# Power_Board.net
KiCad netlist of a schematic drawn in EAGLE
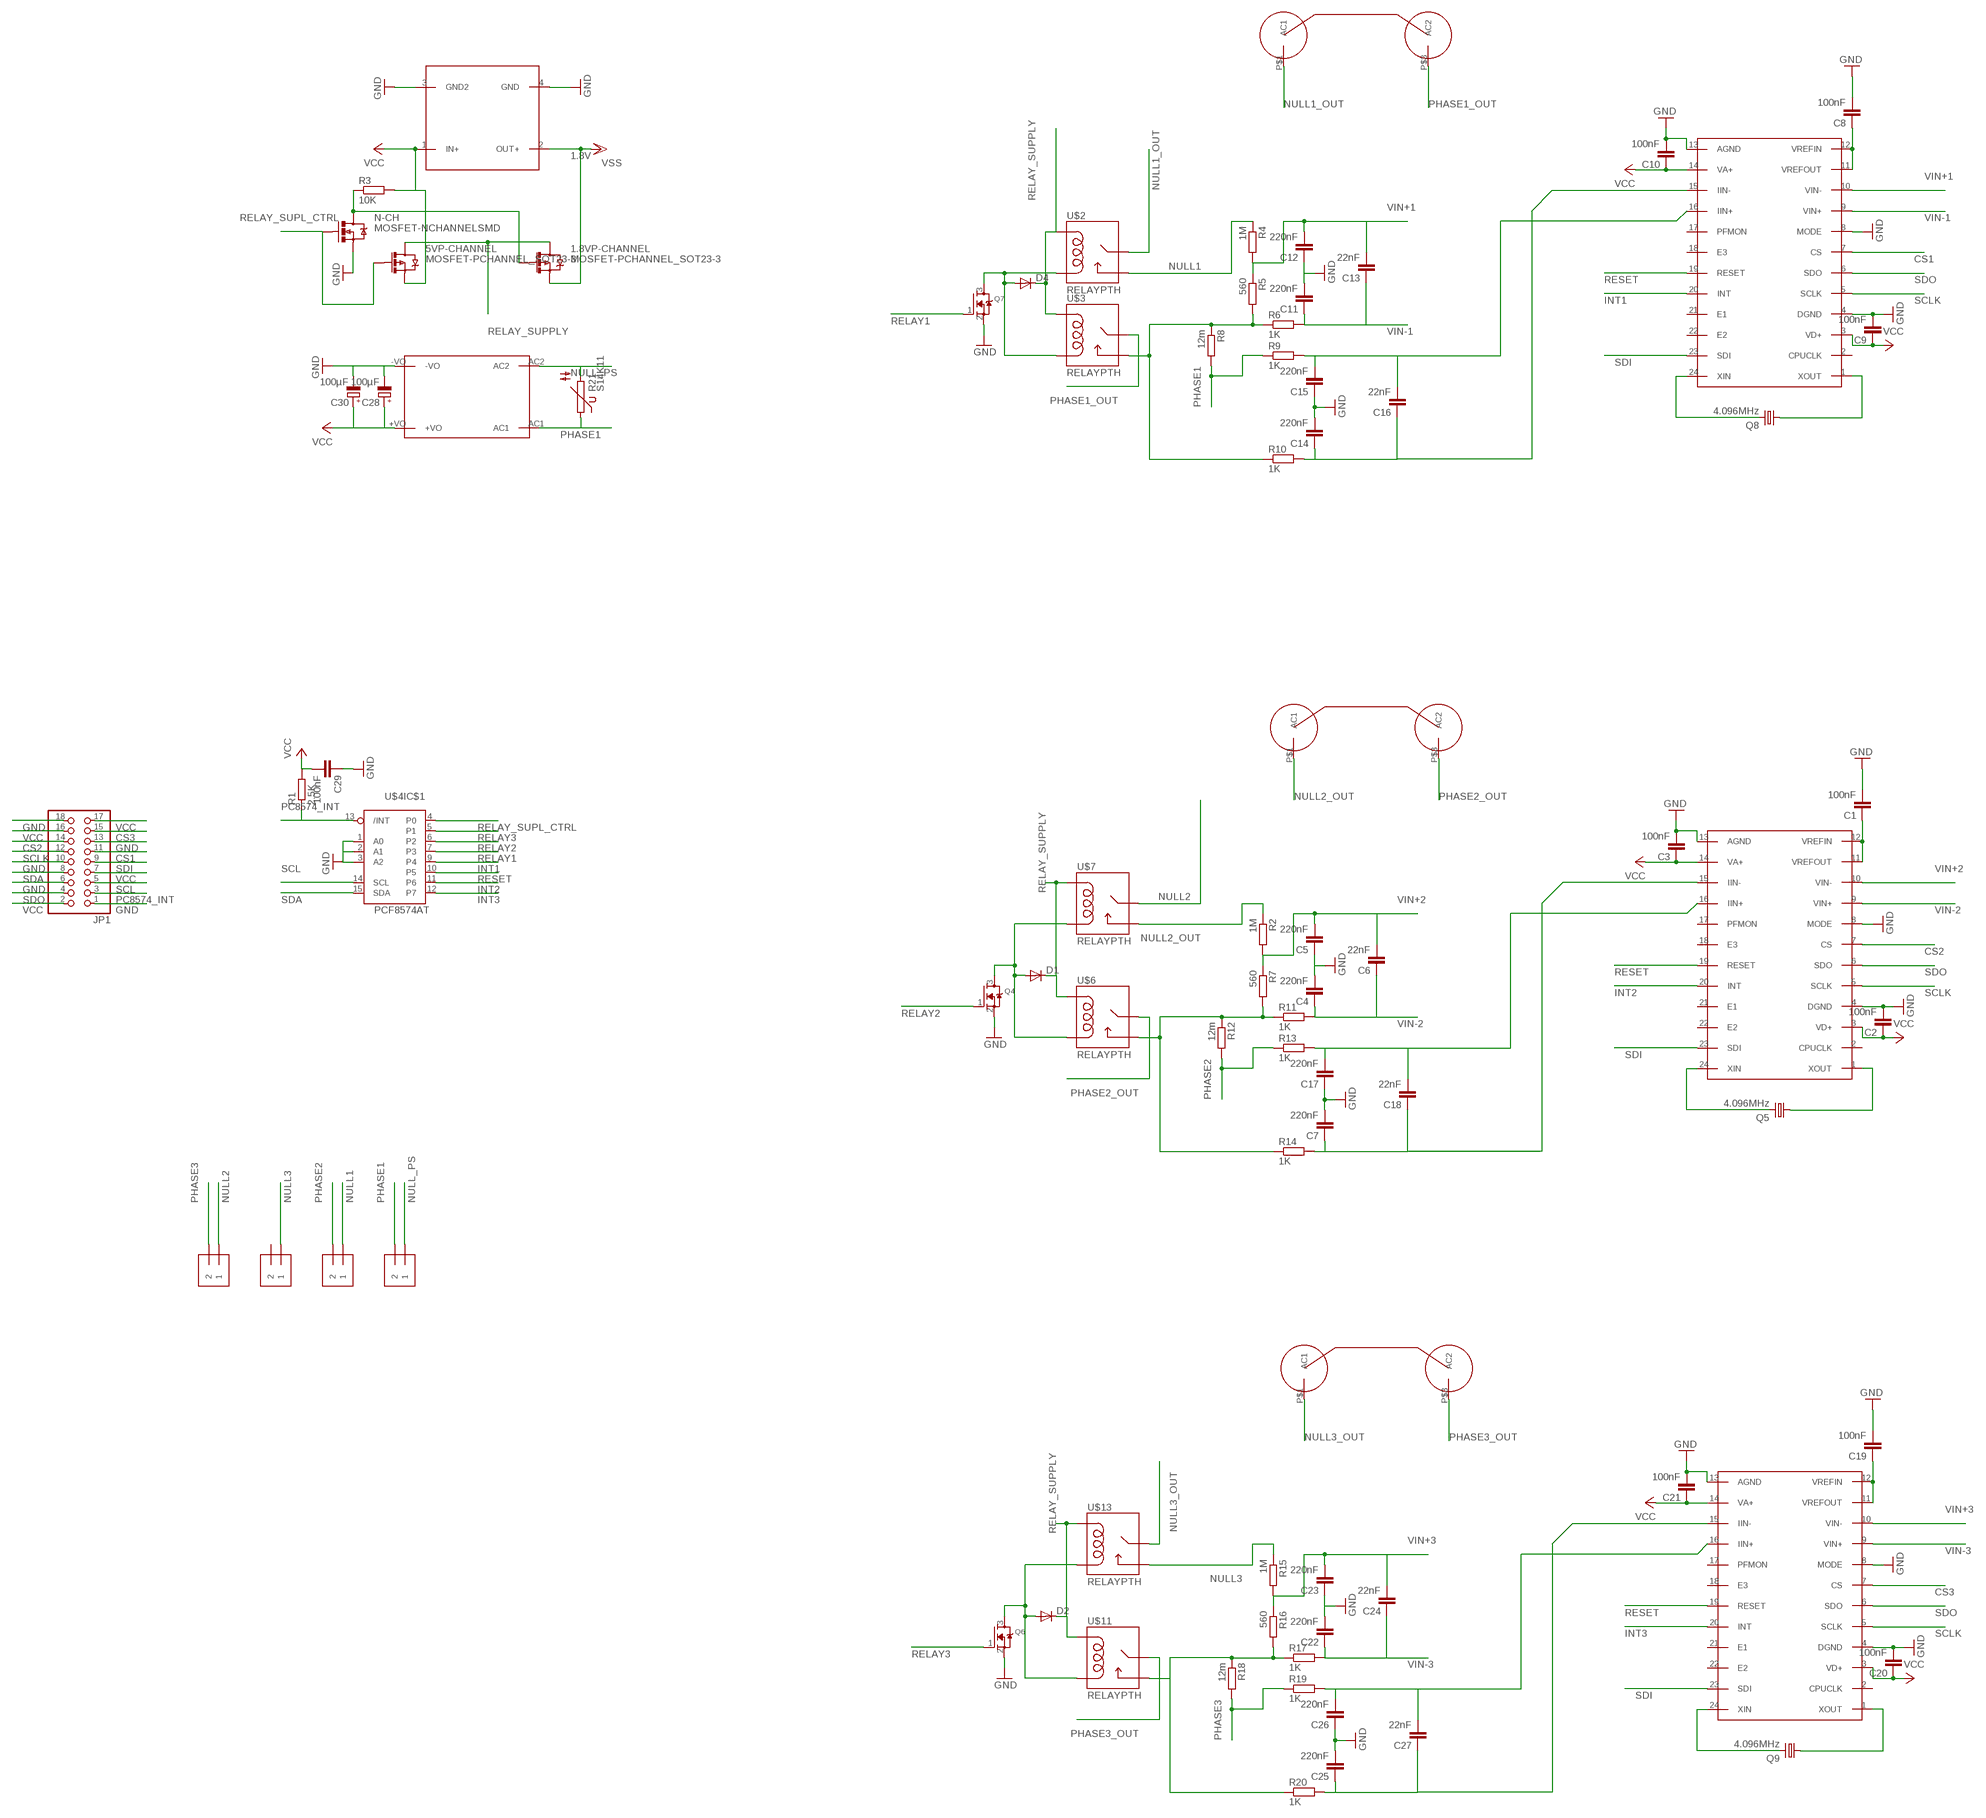
[diagram p0: schematic, sheet 1]

(export (version "E")
  (design (tool "Eeschema 10.0.6"))
  (components
    (comp (ref "1.8VP-CHANNEL")
      (value "MOSFET-PCHANNEL_SOT23-3")
      (footprint "eagle-import:SOT23-3")
      (libsource (lib "eagle-import") (part "MOSFET-PCHANNEL_SOT23-3"))
    )
    (comp (ref "5VP-CHANNEL")
      (value "MOSFET-PCHANNEL_SOT23-3")
      (footprint "eagle-import:SOT23-3")
      (libsource (lib "eagle-import") (part "MOSFET-PCHANNEL_SOT23-3"))
    )
    (comp (ref "C1")
      (value "100nF")
      (footprint "eagle-import:C0805")
      (libsource (lib "eagle-import") (part "C-EUC0805"))
    )
    (comp (ref "C2")
      (value "100nF")
      (footprint "eagle-import:C0805")
      (libsource (lib "eagle-import") (part "C-EUC0805"))
    )
    (comp (ref "C3")
      (value "100nF")
      (footprint "eagle-import:C0805")
      (libsource (lib "eagle-import") (part "C-EUC0805"))
    )
    (comp (ref "C4")
      (value "220nF")
      (footprint "eagle-import:C0805")
      (libsource (lib "eagle-import") (part "C-EUC0805"))
    )
    (comp (ref "C5")
      (value "220nF")
      (footprint "eagle-import:C0805")
      (libsource (lib "eagle-import") (part "C-EUC0805"))
    )
    (comp (ref "C6")
      (value "22nF")
      (footprint "eagle-import:C0805")
      (libsource (lib "eagle-import") (part "C-EUC0805"))
    )
    (comp (ref "C7")
      (value "220nF")
      (footprint "eagle-import:C0805")
      (libsource (lib "eagle-import") (part "C-EUC0805"))
    )
    (comp (ref "C8")
      (value "100nF")
      (footprint "eagle-import:C0805")
      (libsource (lib "eagle-import") (part "rcl_334_C-EUC0805"))
    )
    (comp (ref "C9")
      (value "100nF")
      (footprint "eagle-import:C0805")
      (libsource (lib "eagle-import") (part "rcl_334_C-EUC0805"))
    )
    (comp (ref "C10")
      (value "100nF")
      (footprint "eagle-import:C0805")
      (libsource (lib "eagle-import") (part "rcl_334_C-EUC0805"))
    )
    (comp (ref "C11")
      (value "220nF")
      (footprint "eagle-import:C0805")
      (libsource (lib "eagle-import") (part "C-EUC0805"))
    )
    (comp (ref "C12")
      (value "220nF")
      (footprint "eagle-import:C0805")
      (libsource (lib "eagle-import") (part "C-EUC0805"))
    )
    (comp (ref "C13")
      (value "22nF")
      (footprint "eagle-import:C0805")
      (libsource (lib "eagle-import") (part "C-EUC0805"))
    )
    (comp (ref "C14")
      (value "220nF")
      (footprint "eagle-import:C0805")
      (libsource (lib "eagle-import") (part "C-EUC0805"))
    )
    (comp (ref "C15")
      (value "220nF")
      (footprint "eagle-import:C0805")
      (libsource (lib "eagle-import") (part "C-EUC0805"))
    )
    (comp (ref "C16")
      (value "22nF")
      (footprint "eagle-import:C0805")
      (libsource (lib "eagle-import") (part "rcl_334_C-EUC0805"))
    )
    (comp (ref "C17")
      (value "220nF")
      (footprint "eagle-import:C0805")
      (libsource (lib "eagle-import") (part "C-EUC0805"))
    )
    (comp (ref "C18")
      (value "22nF")
      (footprint "eagle-import:C0805")
      (libsource (lib "eagle-import") (part "C-EUC0805"))
    )
    (comp (ref "C19")
      (value "100nF")
      (footprint "eagle-import:C0805")
      (libsource (lib "eagle-import") (part "C-EUC0805"))
    )
    (comp (ref "C20")
      (value "100nF")
      (footprint "eagle-import:C0805")
      (libsource (lib "eagle-import") (part "C-EUC0805"))
    )
    (comp (ref "C21")
      (value "100nF")
      (footprint "eagle-import:C0805")
      (libsource (lib "eagle-import") (part "rcl_334_C-EUC0805"))
    )
    (comp (ref "C22")
      (value "220nF")
      (footprint "eagle-import:C0805")
      (libsource (lib "eagle-import") (part "rcl_334_C-EUC0805"))
    )
    (comp (ref "C23")
      (value "220nF")
      (footprint "eagle-import:C0805")
      (libsource (lib "eagle-import") (part "C-EUC0805"))
    )
    (comp (ref "C24")
      (value "22nF")
      (footprint "eagle-import:C0805")
      (libsource (lib "eagle-import") (part "C-EUC0805"))
    )
    (comp (ref "C25")
      (value "220nF")
      (footprint "eagle-import:C0805")
      (libsource (lib "eagle-import") (part "C-EUC0805"))
    )
    (comp (ref "C26")
      (value "220nF")
      (footprint "eagle-import:C0805")
      (libsource (lib "eagle-import") (part "C-EUC0805"))
    )
    (comp (ref "C27")
      (value "22nF")
      (footprint "eagle-import:C0805")
      (libsource (lib "eagle-import") (part "C-EUC0805"))
    )
    (comp (ref "C28")
      (value "100µF")
      (footprint "eagle-import:E5-6")
      (libsource (lib "eagle-import") (part "CPOL-EUE5-6"))
    )
    (comp (ref "C29")
      (value "100nF")
      (footprint "eagle-import:C0805")
      (libsource (lib "eagle-import") (part "C-EUC0805"))
    )
    (comp (ref "C30")
      (value "100µF")
      (footprint "eagle-import:E5-6")
      (libsource (lib "eagle-import") (part "CPOL-EUE5-6"))
    )
    (comp (ref "D1")
      (value "DIODE-DO-214AC")
      (footprint "eagle-import:DO-214AC")
      (libsource (lib "eagle-import") (part "DIODE-DO-214AC"))
    )
    (comp (ref "D2")
      (value "DIODE-DO-214AC")
      (footprint "eagle-import:DO-214AC")
      (libsource (lib "eagle-import") (part "DIODE-DO-214AC"))
    )
    (comp (ref "D4")
      (value "DIODE-DO-214AC")
      (footprint "eagle-import:DO-214AC")
      (libsource (lib "eagle-import") (part "DIODE-DO-214AC"))
    )
    (comp (ref "J1")
      (value "1X2-3.5MM")
      (footprint "eagle-import:1X2-3.5MM")
      (libsource (lib "eagle-import") (part "1X2-3.5MM"))
    )
    (comp (ref "J2")
      (value "1X2-3.5MM")
      (footprint "eagle-import:1X2-3.5MM")
      (libsource (lib "eagle-import") (part "1X2-3.5MM"))
    )
    (comp (ref "J3")
      (value "1X2-3.5MM")
      (footprint "eagle-import:1X2-3.5MM")
      (libsource (lib "eagle-import") (part "1X2-3.5MM"))
    )
    (comp (ref "J4")
      (value "1X2-3.5MM")
      (footprint "eagle-import:1X2-3.5MM")
      (libsource (lib "eagle-import") (part "1X2-3.5MM"))
    )
    (comp (ref "JP1")
      (value "PINHD-2X9")
      (footprint "eagle-import:2X09")
      (libsource (lib "eagle-import") (part "PINHD-2X9"))
    )
    (comp (ref "N-CH")
      (value "MOSFET-NCHANNELSMD")
      (footprint "eagle-import:SOT23-3")
      (libsource (lib "eagle-import") (part "MOSFET-NCHANNELSMD"))
    )
    (comp (ref "Q4")
      (value "MOSFET-NREFLOW")
      (footprint "eagle-import:SOT23")
      (libsource (lib "eagle-import") (part "MOSFET-NREFLOW"))
    )
    (comp (ref "Q5")
      (value "4.096MHz")
      (footprint "eagle-import:HC49U70")
      (libsource (lib "eagle-import") (part "CRYSTALHC49U70"))
    )
    (comp (ref "Q6")
      (value "MOSFET-NREFLOW")
      (footprint "eagle-import:SOT23")
      (libsource (lib "eagle-import") (part "MOSFET-NREFLOW"))
    )
    (comp (ref "Q7")
      (value "MOSFET-NREFLOW")
      (footprint "eagle-import:SOT23")
      (libsource (lib "eagle-import") (part "MOSFET-NREFLOW"))
    )
    (comp (ref "Q8")
      (value "4.096MHz")
      (footprint "eagle-import:HC49U70")
      (libsource (lib "eagle-import") (part "CRYSTALHC49U70"))
    )
    (comp (ref "Q9")
      (value "4.096MHz")
      (footprint "eagle-import:HC49U70")
      (libsource (lib "eagle-import") (part "CRYSTALHC49U70"))
    )
    (comp (ref "R1")
      (value "2.5K")
      (footprint "eagle-import:R0805")
      (libsource (lib "eagle-import") (part "resistor_348_R-EU_R0805"))
    )
    (comp (ref "R2")
      (value "1M")
      (footprint "eagle-import:R0805")
      (libsource (lib "eagle-import") (part "R-EU_R0805"))
    )
    (comp (ref "R3")
      (value "10K")
      (footprint "eagle-import:R0805")
      (libsource (lib "eagle-import") (part "resistor_348_R-EU_R0805"))
    )
    (comp (ref "R4")
      (value "1M")
      (footprint "eagle-import:R0805")
      (libsource (lib "eagle-import") (part "R-EU_R0805"))
    )
    (comp (ref "R5")
      (value "560")
      (footprint "eagle-import:R1206")
      (libsource (lib "eagle-import") (part "R-EU_R1206"))
    )
    (comp (ref "R6")
      (value "1K")
      (footprint "eagle-import:R0805")
      (libsource (lib "eagle-import") (part "R-EU_R0805"))
    )
    (comp (ref "R7")
      (value "560")
      (footprint "eagle-import:R1206")
      (libsource (lib "eagle-import") (part "R-EU_R1206"))
    )
    (comp (ref "R8")
      (value "12m")
      (footprint "eagle-import:R2512")
      (libsource (lib "eagle-import") (part "R-EU_R2512"))
    )
    (comp (ref "R9")
      (value "1K")
      (footprint "eagle-import:R0805")
      (libsource (lib "eagle-import") (part "R-EU_R0805"))
    )
    (comp (ref "R10")
      (value "1K")
      (footprint "eagle-import:R0805")
      (libsource (lib "eagle-import") (part "R-EU_R0805"))
    )
    (comp (ref "R11")
      (value "1K")
      (footprint "eagle-import:R0805")
      (libsource (lib "eagle-import") (part "R-EU_R0805"))
    )
    (comp (ref "R12")
      (value "12m")
      (footprint "eagle-import:R2512")
      (libsource (lib "eagle-import") (part "R-EU_R2512"))
    )
    (comp (ref "R13")
      (value "1K")
      (footprint "eagle-import:R0805")
      (libsource (lib "eagle-import") (part "R-EU_R0805"))
    )
    (comp (ref "R14")
      (value "1K")
      (footprint "eagle-import:R0805")
      (libsource (lib "eagle-import") (part "R-EU_R0805"))
    )
    (comp (ref "R15")
      (value "1M")
      (footprint "eagle-import:R0805")
      (libsource (lib "eagle-import") (part "R-EU_R0805"))
    )
    (comp (ref "R16")
      (value "560")
      (footprint "eagle-import:R1206")
      (libsource (lib "eagle-import") (part "R-EU_R1206"))
    )
    (comp (ref "R17")
      (value "1K")
      (footprint "eagle-import:R0805")
      (libsource (lib "eagle-import") (part "R-EU_R0805"))
    )
    (comp (ref "R18")
      (value "12m")
      (footprint "eagle-import:R2512")
      (libsource (lib "eagle-import") (part "R-EU_R2512"))
    )
    (comp (ref "R19")
      (value "1K")
      (footprint "eagle-import:R0805")
      (libsource (lib "eagle-import") (part "R-EU_R0805"))
    )
    (comp (ref "R20")
      (value "1K")
      (footprint "eagle-import:R0805")
      (libsource (lib "eagle-import") (part "R-EU_R0805"))
    )
    (comp (ref "R21")
      (value "S14K11")
      (footprint "eagle-import:S14K11")
      (libsource (lib "eagle-import") (part "S14K11"))
    )
    (comp (ref "U$1")
      (value "STEP_DOWN")
      (footprint "eagle-import:STEP_DOWN")
      (libsource (lib "eagle-import") (part "STEP_DOWN"))
    )
    (comp (ref "U$2")
      (value "RELAYPTH")
      (footprint "eagle-import:SRD-05VDC-SL-C")
      (libsource (lib "eagle-import") (part "RELAYPTH"))
    )
    (comp (ref "U$3")
      (value "RELAYPTH")
      (footprint "eagle-import:SRD-05VDC-SL-C")
      (libsource (lib "eagle-import") (part "RELAYPTH"))
    )
    (comp (ref "U$4")
      (value "PCF8574AT")
      (footprint "eagle-import:SO16")
      (libsource (lib "eagle-import") (part "PCF8574AT"))
    )
    (comp (ref "U$5")
      (value "HLK-PM03")
      (footprint "eagle-import:HLK-PM03")
      (libsource (lib "eagle-import") (part "HLK-PM03"))
    )
    (comp (ref "U$6")
      (value "RELAYPTH")
      (footprint "eagle-import:SRD-05VDC-SL-C")
      (libsource (lib "eagle-import") (part "RELAYPTH"))
    )
    (comp (ref "U$7")
      (value "RELAYPTH")
      (footprint "eagle-import:SRD-05VDC-SL-C")
      (libsource (lib "eagle-import") (part "RELAYPTH"))
    )
    (comp (ref "U$8")
      (value "CS5463")
      (footprint "eagle-import:SSOP24")
      (libsource (lib "eagle-import") (part "CS5463"))
    )
    (comp (ref "U$9")
      (value "CS5463")
      (footprint "eagle-import:SSOP24")
      (libsource (lib "eagle-import") (part "CS5463"))
    )
    (comp (ref "U$10")
      (value "POWER_SOCKET_EU")
      (footprint "eagle-import:POWER_SOCKET_EU_PLATED_THROUGH")
      (libsource (lib "eagle-import") (part "POWER_SOCKET_EU"))
    )
    (comp (ref "U$11")
      (value "RELAYPTH")
      (footprint "eagle-import:SRD-05VDC-SL-C")
      (libsource (lib "eagle-import") (part "RELAYPTH"))
    )
    (comp (ref "U$12")
      (value "POWER_SOCKET_EU")
      (footprint "eagle-import:POWER_SOCKET_EU_PLATED_THROUGH")
      (libsource (lib "eagle-import") (part "POWER_SOCKET_EU"))
    )
    (comp (ref "U$13")
      (value "RELAYPTH")
      (footprint "eagle-import:SRD-05VDC-SL-C")
      (libsource (lib "eagle-import") (part "RELAYPTH"))
    )
    (comp (ref "U$14")
      (value "CS5463")
      (footprint "eagle-import:SSOP24")
      (libsource (lib "eagle-import") (part "CS5463"))
    )
    (comp (ref "U$15")
      (value "POWER_SOCKET_EU")
      (footprint "eagle-import:POWER_SOCKET_EU_PLATED_THROUGH")
      (libsource (lib "eagle-import") (part "POWER_SOCKET_EU"))
    )
  )
  (nets
    (net (code "1") (name "/CS1") (class "Default")
      (node (ref "JP1") (pin "11") (pinfunction "11_11") (pintype "passive"))
      (node (ref "U$9") (pin "7") (pinfunction "CS_7") (pintype "bidirectional"))
    )
    (net (code "2") (name "/CS2") (class "Default")
      (node (ref "JP1") (pin "14") (pinfunction "14_14") (pintype "passive"))
      (node (ref "U$8") (pin "7") (pinfunction "CS_7") (pintype "bidirectional"))
    )
    (net (code "3") (name "/CS3") (class "Default")
      (node (ref "JP1") (pin "15") (pinfunction "15_15") (pintype "passive"))
      (node (ref "U$14") (pin "7") (pinfunction "CS_7") (pintype "bidirectional"))
    )
    (net (code "4") (name "/INT1") (class "Default")
      (node (ref "U$4") (pin "9") (pinfunction "P4_9") (pintype "bidirectional"))
      (node (ref "U$9") (pin "20") (pinfunction "INT_20") (pintype "bidirectional"))
    )
    (net (code "5") (name "/INT2") (class "Default")
      (node (ref "U$4") (pin "11") (pinfunction "P6_11") (pintype "bidirectional"))
      (node (ref "U$8") (pin "20") (pinfunction "INT_20") (pintype "bidirectional"))
    )
    (net (code "6") (name "/INT3") (class "Default")
      (node (ref "U$14") (pin "20") (pinfunction "INT_20") (pintype "bidirectional"))
      (node (ref "U$4") (pin "12") (pinfunction "P7_12") (pintype "bidirectional"))
    )
    (net (code "7") (name "/NULL1") (class "Default")
      (node (ref "J2") (pin "1") (pinfunction "1_1") (pintype "passive"))
      (node (ref "R4") (pin "1") (pinfunction "1_1") (pintype "passive"))
      (node (ref "U$2") (pin "SWOPEN") (pinfunction "SWOPEN_SWOPEN") (pintype "bidirectional"))
    )
    (net (code "8") (name "/NULL1_OUT") (class "Default")
      (node (ref "U$12") (pin "P$1") (pinfunction "AC1_P$1") (pintype "bidirectional"))
      (node (ref "U$2") (pin "SWCOMMON") (pinfunction "SWCOMMON_SWCOMMON") (pintype "bidirectional"))
    )
    (net (code "9") (name "/NULL2") (class "Default")
      (node (ref "J1") (pin "1") (pinfunction "1_1") (pintype "passive"))
      (node (ref "R2") (pin "1") (pinfunction "1_1") (pintype "passive"))
      (node (ref "U$7") (pin "SWOPEN") (pinfunction "SWOPEN_SWOPEN") (pintype "bidirectional"))
    )
    (net (code "10") (name "/NULL2_OUT") (class "Default")
      (node (ref "U$10") (pin "P$1") (pinfunction "AC1_P$1") (pintype "bidirectional"))
      (node (ref "U$7") (pin "SWCOMMON") (pinfunction "SWCOMMON_SWCOMMON") (pintype "bidirectional"))
    )
    (net (code "11") (name "/NULL3") (class "Default")
      (node (ref "J3") (pin "1") (pinfunction "1_1") (pintype "passive"))
      (node (ref "R15") (pin "1") (pinfunction "1_1") (pintype "passive"))
      (node (ref "U$13") (pin "SWOPEN") (pinfunction "SWOPEN_SWOPEN") (pintype "bidirectional"))
    )
    (net (code "12") (name "/NULL3_OUT") (class "Default")
      (node (ref "U$13") (pin "SWCOMMON") (pinfunction "SWCOMMON_SWCOMMON") (pintype "bidirectional"))
      (node (ref "U$15") (pin "P$1") (pinfunction "AC1_P$1") (pintype "bidirectional"))
    )
    (net (code "13") (name "/NULL_PS") (class "Default")
      (node (ref "J4") (pin "1") (pinfunction "1_1") (pintype "passive"))
      (node (ref "R21") (pin "2") (pinfunction "2_2") (pintype "passive"))
      (node (ref "U$5") (pin "AC2") (pinfunction "AC2_AC2") (pintype "bidirectional"))
    )
    (net (code "14") (name "/PC8574_INT") (class "Default")
      (node (ref "JP1") (pin "3") (pinfunction "3_3") (pintype "passive"))
      (node (ref "R1") (pin "1") (pinfunction "1_1") (pintype "passive"))
      (node (ref "U$4") (pin "13") (pinfunction "/INT_13") (pintype "output"))
    )
    (net (code "15") (name "/PHASE1") (class "Default")
      (node (ref "J4") (pin "2") (pinfunction "2_2") (pintype "passive"))
      (node (ref "R21") (pin "1") (pinfunction "1_1") (pintype "passive"))
      (node (ref "R8") (pin "2") (pinfunction "2_2") (pintype "passive"))
      (node (ref "R9") (pin "1") (pinfunction "1_1") (pintype "passive"))
      (node (ref "U$5") (pin "AC1") (pinfunction "AC1_AC1") (pintype "bidirectional"))
    )
    (net (code "16") (name "/PHASE1_OUT") (class "Default")
      (node (ref "U$12") (pin "P$3") (pinfunction "AC2_P$3") (pintype "bidirectional"))
      (node (ref "U$3") (pin "SWCOMMON") (pinfunction "SWCOMMON_SWCOMMON") (pintype "bidirectional"))
    )
    (net (code "17") (name "/PHASE2") (class "Default")
      (node (ref "J2") (pin "2") (pinfunction "2_2") (pintype "passive"))
      (node (ref "R12") (pin "2") (pinfunction "2_2") (pintype "passive"))
      (node (ref "R13") (pin "1") (pinfunction "1_1") (pintype "passive"))
    )
    (net (code "18") (name "/PHASE2_OUT") (class "Default")
      (node (ref "U$10") (pin "P$3") (pinfunction "AC2_P$3") (pintype "bidirectional"))
      (node (ref "U$6") (pin "SWCOMMON") (pinfunction "SWCOMMON_SWCOMMON") (pintype "bidirectional"))
    )
    (net (code "19") (name "/PHASE3") (class "Default")
      (node (ref "J1") (pin "2") (pinfunction "2_2") (pintype "passive"))
      (node (ref "R18") (pin "2") (pinfunction "2_2") (pintype "passive"))
      (node (ref "R19") (pin "1") (pinfunction "1_1") (pintype "passive"))
    )
    (net (code "20") (name "/PHASE3_OUT") (class "Default")
      (node (ref "U$11") (pin "SWCOMMON") (pinfunction "SWCOMMON_SWCOMMON") (pintype "bidirectional"))
      (node (ref "U$15") (pin "P$3") (pinfunction "AC2_P$3") (pintype "bidirectional"))
    )
    (net (code "21") (name "/RELAY1") (class "Default")
      (node (ref "Q7") (pin "1") (pinfunction "G_1") (pintype "bidirectional"))
      (node (ref "U$4") (pin "7") (pinfunction "P3_7") (pintype "bidirectional"))
    )
    (net (code "22") (name "/RELAY2") (class "Default")
      (node (ref "Q4") (pin "1") (pinfunction "G_1") (pintype "bidirectional"))
      (node (ref "U$4") (pin "6") (pinfunction "P2_6") (pintype "bidirectional"))
    )
    (net (code "23") (name "/RELAY3") (class "Default")
      (node (ref "Q6") (pin "1") (pinfunction "G_1") (pintype "bidirectional"))
      (node (ref "U$4") (pin "5") (pinfunction "P1_5") (pintype "bidirectional"))
    )
    (net (code "24") (name "/RELAY_SUPL_CTRL") (class "Default")
      (node (ref "5VP-CHANNEL") (pin "1") (pinfunction "G_1") (pintype "passive"))
      (node (ref "N-CH") (pin "1") (pinfunction "G_1") (pintype "passive"))
      (node (ref "U$4") (pin "4") (pinfunction "P0_4") (pintype "bidirectional"))
    )
    (net (code "25") (name "/RELAY_SUPPLY") (class "Default")
      (node (ref "1.8VP-CHANNEL") (pin "3") (pinfunction "D_3") (pintype "passive"))
      (node (ref "5VP-CHANNEL") (pin "3") (pinfunction "D_3") (pintype "passive"))
      (node (ref "D1") (pin "C") (pinfunction "C_C") (pintype "passive"))
      (node (ref "D2") (pin "C") (pinfunction "C_C") (pintype "passive"))
      (node (ref "D4") (pin "C") (pinfunction "C_C") (pintype "passive"))
      (node (ref "U$11") (pin "COIL1") (pinfunction "COIL1_COIL1") (pintype "bidirectional"))
      (node (ref "U$13") (pin "COIL1") (pinfunction "COIL1_COIL1") (pintype "bidirectional"))
      (node (ref "U$2") (pin "COIL1") (pinfunction "COIL1_COIL1") (pintype "bidirectional"))
      (node (ref "U$3") (pin "COIL1") (pinfunction "COIL1_COIL1") (pintype "bidirectional"))
      (node (ref "U$6") (pin "COIL1") (pinfunction "COIL1_COIL1") (pintype "bidirectional"))
      (node (ref "U$7") (pin "COIL1") (pinfunction "COIL1_COIL1") (pintype "bidirectional"))
    )
    (net (code "26") (name "/RESET") (class "Default")
      (node (ref "U$14") (pin "19") (pinfunction "RESET_19") (pintype "bidirectional"))
      (node (ref "U$4") (pin "10") (pinfunction "P5_10") (pintype "bidirectional"))
      (node (ref "U$8") (pin "19") (pinfunction "RESET_19") (pintype "bidirectional"))
      (node (ref "U$9") (pin "19") (pinfunction "RESET_19") (pintype "bidirectional"))
    )
    (net (code "27") (name "/SCL") (class "Default")
      (node (ref "JP1") (pin "5") (pinfunction "5_5") (pintype "passive"))
      (node (ref "U$4") (pin "14") (pinfunction "SCL_14") (pintype "input"))
    )
    (net (code "28") (name "/SCLK") (class "Default")
      (node (ref "JP1") (pin "12") (pinfunction "12_12") (pintype "passive"))
      (node (ref "U$14") (pin "5") (pinfunction "SCLK_5") (pintype "bidirectional"))
      (node (ref "U$8") (pin "5") (pinfunction "SCLK_5") (pintype "bidirectional"))
      (node (ref "U$9") (pin "5") (pinfunction "SCLK_5") (pintype "bidirectional"))
    )
    (net (code "29") (name "/SDA") (class "Default")
      (node (ref "JP1") (pin "8") (pinfunction "8_8") (pintype "passive"))
      (node (ref "U$4") (pin "15") (pinfunction "SDA_15") (pintype "bidirectional"))
    )
    (net (code "30") (name "/SDI") (class "Default")
      (node (ref "JP1") (pin "9") (pinfunction "9_9") (pintype "passive"))
      (node (ref "U$14") (pin "23") (pinfunction "SDI_23") (pintype "bidirectional"))
      (node (ref "U$8") (pin "23") (pinfunction "SDI_23") (pintype "bidirectional"))
      (node (ref "U$9") (pin "23") (pinfunction "SDI_23") (pintype "bidirectional"))
    )
    (net (code "31") (name "/SDO") (class "Default")
      (node (ref "JP1") (pin "4") (pinfunction "4_4") (pintype "passive"))
      (node (ref "U$14") (pin "6") (pinfunction "SDO_6") (pintype "bidirectional"))
      (node (ref "U$8") (pin "6") (pinfunction "SDO_6") (pintype "bidirectional"))
      (node (ref "U$9") (pin "6") (pinfunction "SDO_6") (pintype "bidirectional"))
    )
    (net (code "32") (name "/VIN+1") (class "Default")
      (node (ref "C12") (pin "2") (pinfunction "2_2") (pintype "passive"))
      (node (ref "C13") (pin "2") (pinfunction "2_2") (pintype "passive"))
      (node (ref "R4") (pin "2") (pinfunction "2_2") (pintype "passive"))
      (node (ref "R5") (pin "1") (pinfunction "1_1") (pintype "passive"))
      (node (ref "U$9") (pin "10") (pinfunction "VIN-_10") (pintype "bidirectional"))
    )
    (net (code "33") (name "/VIN+2") (class "Default")
      (node (ref "C5") (pin "2") (pinfunction "2_2") (pintype "passive"))
      (node (ref "C6") (pin "2") (pinfunction "2_2") (pintype "passive"))
      (node (ref "R2") (pin "2") (pinfunction "2_2") (pintype "passive"))
      (node (ref "R7") (pin "1") (pinfunction "1_1") (pintype "passive"))
      (node (ref "U$8") (pin "10") (pinfunction "VIN-_10") (pintype "bidirectional"))
    )
    (net (code "34") (name "/VIN+3") (class "Default")
      (node (ref "C23") (pin "2") (pinfunction "2_2") (pintype "passive"))
      (node (ref "C24") (pin "2") (pinfunction "2_2") (pintype "passive"))
      (node (ref "R15") (pin "2") (pinfunction "2_2") (pintype "passive"))
      (node (ref "R16") (pin "1") (pinfunction "1_1") (pintype "passive"))
      (node (ref "U$14") (pin "10") (pinfunction "VIN-_10") (pintype "bidirectional"))
    )
    (net (code "35") (name "/VIN-1") (class "Default")
      (node (ref "C11") (pin "1") (pinfunction "1_1") (pintype "passive"))
      (node (ref "C13") (pin "1") (pinfunction "1_1") (pintype "passive"))
      (node (ref "R6") (pin "2") (pinfunction "2_2") (pintype "passive"))
      (node (ref "U$9") (pin "9") (pinfunction "VIN+_9") (pintype "bidirectional"))
    )
    (net (code "36") (name "/VIN-2") (class "Default")
      (node (ref "C4") (pin "1") (pinfunction "1_1") (pintype "passive"))
      (node (ref "C6") (pin "1") (pinfunction "1_1") (pintype "passive"))
      (node (ref "R11") (pin "2") (pinfunction "2_2") (pintype "passive"))
      (node (ref "U$8") (pin "9") (pinfunction "VIN+_9") (pintype "bidirectional"))
    )
    (net (code "37") (name "/VIN-3") (class "Default")
      (node (ref "C22") (pin "1") (pinfunction "1_1") (pintype "passive"))
      (node (ref "C24") (pin "1") (pinfunction "1_1") (pintype "passive"))
      (node (ref "R17") (pin "2") (pinfunction "2_2") (pintype "passive"))
      (node (ref "U$14") (pin "9") (pinfunction "VIN+_9") (pintype "bidirectional"))
    )
    (net (code "38") (name "GND") (class "Default")
      (node (ref "C1") (pin "2") (pinfunction "2_2") (pintype "passive"))
      (node (ref "C10") (pin "2") (pinfunction "2_2") (pintype "passive"))
      (node (ref "C11") (pin "2") (pinfunction "2_2") (pintype "passive"))
      (node (ref "C12") (pin "1") (pinfunction "1_1") (pintype "passive"))
      (node (ref "C14") (pin "2") (pinfunction "2_2") (pintype "passive"))
      (node (ref "C15") (pin "1") (pinfunction "1_1") (pintype "passive"))
      (node (ref "C17") (pin "1") (pinfunction "1_1") (pintype "passive"))
      (node (ref "C19") (pin "2") (pinfunction "2_2") (pintype "passive"))
      (node (ref "C2") (pin "2") (pinfunction "2_2") (pintype "passive"))
      (node (ref "C20") (pin "2") (pinfunction "2_2") (pintype "passive"))
      (node (ref "C21") (pin "2") (pinfunction "2_2") (pintype "passive"))
      (node (ref "C22") (pin "2") (pinfunction "2_2") (pintype "passive"))
      (node (ref "C23") (pin "1") (pinfunction "1_1") (pintype "passive"))
      (node (ref "C25") (pin "2") (pinfunction "2_2") (pintype "passive"))
      (node (ref "C26") (pin "1") (pinfunction "1_1") (pintype "passive"))
      (node (ref "C28") (pin "-") (pinfunction "-_-") (pintype "passive"))
      (node (ref "C29") (pin "1") (pinfunction "1_1") (pintype "passive"))
      (node (ref "C3") (pin "2") (pinfunction "2_2") (pintype "passive"))
      (node (ref "C30") (pin "-") (pinfunction "-_-") (pintype "passive"))
      (node (ref "C4") (pin "2") (pinfunction "2_2") (pintype "passive"))
      (node (ref "C5") (pin "1") (pinfunction "1_1") (pintype "passive"))
      (node (ref "C7") (pin "2") (pinfunction "2_2") (pintype "passive"))
      (node (ref "C8") (pin "2") (pinfunction "2_2") (pintype "passive"))
      (node (ref "C9") (pin "2") (pinfunction "2_2") (pintype "passive"))
      (node (ref "JP1") (pin "1") (pinfunction "1_1") (pintype "passive"))
      (node (ref "JP1") (pin "10") (pinfunction "10_10") (pintype "passive"))
      (node (ref "JP1") (pin "13") (pinfunction "13_13") (pintype "passive"))
      (node (ref "JP1") (pin "18") (pinfunction "18_18") (pintype "passive"))
      (node (ref "JP1") (pin "6") (pinfunction "6_6") (pintype "passive"))
      (node (ref "N-CH") (pin "2") (pinfunction "S_2") (pintype "passive"))
      (node (ref "Q4") (pin "2") (pinfunction "S_2") (pintype "bidirectional"))
      (node (ref "Q6") (pin "2") (pinfunction "S_2") (pintype "bidirectional"))
      (node (ref "Q7") (pin "2") (pinfunction "S_2") (pintype "bidirectional"))
      (node (ref "U$1") (pin "3") (pinfunction "GND2_3") (pintype "bidirectional"))
      (node (ref "U$1") (pin "4") (pinfunction "GND_4") (pintype "bidirectional"))
      (node (ref "U$14") (pin "13") (pinfunction "AGND_13") (pintype "bidirectional"))
      (node (ref "U$14") (pin "4") (pinfunction "DGND_4") (pintype "bidirectional"))
      (node (ref "U$14") (pin "8") (pinfunction "MODE_8") (pintype "bidirectional"))
      (node (ref "U$4") (pin "1") (pinfunction "A0_1") (pintype "input"))
      (node (ref "U$4") (pin "2") (pinfunction "A1_2") (pintype "input"))
      (node (ref "U$4") (pin "3") (pinfunction "A2_3") (pintype "input"))
      (node (ref "U$5") (pin "-VO") (pinfunction "-VO_-VO") (pintype "bidirectional"))
      (node (ref "U$8") (pin "13") (pinfunction "AGND_13") (pintype "bidirectional"))
      (node (ref "U$8") (pin "4") (pinfunction "DGND_4") (pintype "bidirectional"))
      (node (ref "U$8") (pin "8") (pinfunction "MODE_8") (pintype "bidirectional"))
      (node (ref "U$9") (pin "13") (pinfunction "AGND_13") (pintype "bidirectional"))
      (node (ref "U$9") (pin "4") (pinfunction "DGND_4") (pintype "bidirectional"))
      (node (ref "U$9") (pin "8") (pinfunction "MODE_8") (pintype "bidirectional"))
    )
    (net (code "39") (name "Net-(1.8VP-CHANNEL-G)") (class "Default")
      (node (ref "1.8VP-CHANNEL") (pin "1") (pinfunction "G_1") (pintype "passive"))
      (node (ref "N-CH") (pin "3") (pinfunction "D_3") (pintype "passive"))
      (node (ref "R3") (pin "1") (pinfunction "1_1") (pintype "passive"))
    )
    (net (code "40") (name "Net-(Q4-D)") (class "Default")
      (node (ref "D1") (pin "A") (pinfunction "A_A") (pintype "passive"))
      (node (ref "Q4") (pin "3") (pinfunction "D_3") (pintype "bidirectional"))
      (node (ref "U$6") (pin "COIL0") (pinfunction "COIL0_COIL0") (pintype "bidirectional"))
      (node (ref "U$7") (pin "COIL0") (pinfunction "COIL0_COIL0") (pintype "bidirectional"))
    )
    (net (code "41") (name "Net-(Q6-D)") (class "Default")
      (node (ref "D2") (pin "A") (pinfunction "A_A") (pintype "passive"))
      (node (ref "Q6") (pin "3") (pinfunction "D_3") (pintype "bidirectional"))
      (node (ref "U$11") (pin "COIL0") (pinfunction "COIL0_COIL0") (pintype "bidirectional"))
      (node (ref "U$13") (pin "COIL0") (pinfunction "COIL0_COIL0") (pintype "bidirectional"))
    )
    (net (code "42") (name "Net-(Q7-D)") (class "Default")
      (node (ref "D4") (pin "A") (pinfunction "A_A") (pintype "passive"))
      (node (ref "Q7") (pin "3") (pinfunction "D_3") (pintype "bidirectional"))
      (node (ref "U$2") (pin "COIL0") (pinfunction "COIL0_COIL0") (pintype "bidirectional"))
      (node (ref "U$3") (pin "COIL0") (pinfunction "COIL0_COIL0") (pintype "bidirectional"))
    )
    (net (code "43") (name "Net-(R10-Pad1)") (class "Default")
      (node (ref "R10") (pin "1") (pinfunction "1_1") (pintype "passive"))
      (node (ref "R5") (pin "2") (pinfunction "2_2") (pintype "passive"))
      (node (ref "R6") (pin "1") (pinfunction "1_1") (pintype "passive"))
      (node (ref "R8") (pin "1") (pinfunction "1_1") (pintype "passive"))
      (node (ref "U$3") (pin "SWOPEN") (pinfunction "SWOPEN_SWOPEN") (pintype "bidirectional"))
    )
    (net (code "44") (name "Net-(R11-Pad1)") (class "Default")
      (node (ref "R11") (pin "1") (pinfunction "1_1") (pintype "passive"))
      (node (ref "R12") (pin "1") (pinfunction "1_1") (pintype "passive"))
      (node (ref "R14") (pin "1") (pinfunction "1_1") (pintype "passive"))
      (node (ref "R7") (pin "2") (pinfunction "2_2") (pintype "passive"))
      (node (ref "U$6") (pin "SWOPEN") (pinfunction "SWOPEN_SWOPEN") (pintype "bidirectional"))
    )
    (net (code "45") (name "Net-(R16-Pad2)") (class "Default")
      (node (ref "R16") (pin "2") (pinfunction "2_2") (pintype "passive"))
      (node (ref "R17") (pin "1") (pinfunction "1_1") (pintype "passive"))
      (node (ref "R18") (pin "1") (pinfunction "1_1") (pintype "passive"))
      (node (ref "R20") (pin "1") (pinfunction "1_1") (pintype "passive"))
      (node (ref "U$11") (pin "SWOPEN") (pinfunction "SWOPEN_SWOPEN") (pintype "bidirectional"))
    )
    (net (code "46") (name "Net-(U$8-IIN+)") (class "Default")
      (node (ref "C17") (pin "2") (pinfunction "2_2") (pintype "passive"))
      (node (ref "C18") (pin "2") (pinfunction "2_2") (pintype "passive"))
      (node (ref "R13") (pin "2") (pinfunction "2_2") (pintype "passive"))
      (node (ref "U$8") (pin "16") (pinfunction "IIN+_16") (pintype "bidirectional"))
    )
    (net (code "47") (name "Net-(U$8-IIN-)") (class "Default")
      (node (ref "C18") (pin "1") (pinfunction "1_1") (pintype "passive"))
      (node (ref "C7") (pin "1") (pinfunction "1_1") (pintype "passive"))
      (node (ref "R14") (pin "2") (pinfunction "2_2") (pintype "passive"))
      (node (ref "U$8") (pin "15") (pinfunction "IIN-_15") (pintype "bidirectional"))
    )
    (net (code "48") (name "Net-(U$8-VREFIN)") (class "Default")
      (node (ref "C1") (pin "1") (pinfunction "1_1") (pintype "passive"))
      (node (ref "U$8") (pin "11") (pinfunction "VREFOUT_11") (pintype "bidirectional"))
      (node (ref "U$8") (pin "12") (pinfunction "VREFIN_12") (pintype "bidirectional"))
    )
    (net (code "49") (name "Net-(U$8-XIN)") (class "Default")
      (node (ref "Q5") (pin "2") (pinfunction "2_2") (pintype "passive"))
      (node (ref "U$8") (pin "24") (pinfunction "XIN_24") (pintype "bidirectional"))
    )
    (net (code "50") (name "Net-(U$8-XOUT)") (class "Default")
      (node (ref "Q5") (pin "1") (pinfunction "1_1") (pintype "passive"))
      (node (ref "U$8") (pin "1") (pinfunction "XOUT_1") (pintype "bidirectional"))
    )
    (net (code "51") (name "Net-(U$9-IIN+)") (class "Default")
      (node (ref "C15") (pin "2") (pinfunction "2_2") (pintype "passive"))
      (node (ref "C16") (pin "2") (pinfunction "2_2") (pintype "passive"))
      (node (ref "R9") (pin "2") (pinfunction "2_2") (pintype "passive"))
      (node (ref "U$9") (pin "16") (pinfunction "IIN+_16") (pintype "bidirectional"))
    )
    (net (code "52") (name "Net-(U$9-IIN-)") (class "Default")
      (node (ref "C14") (pin "1") (pinfunction "1_1") (pintype "passive"))
      (node (ref "C16") (pin "1") (pinfunction "1_1") (pintype "passive"))
      (node (ref "R10") (pin "2") (pinfunction "2_2") (pintype "passive"))
      (node (ref "U$9") (pin "15") (pinfunction "IIN-_15") (pintype "bidirectional"))
    )
    (net (code "53") (name "Net-(U$9-VREFIN)") (class "Default")
      (node (ref "C8") (pin "1") (pinfunction "1_1") (pintype "passive"))
      (node (ref "U$9") (pin "11") (pinfunction "VREFOUT_11") (pintype "bidirectional"))
      (node (ref "U$9") (pin "12") (pinfunction "VREFIN_12") (pintype "bidirectional"))
    )
    (net (code "54") (name "Net-(U$9-XIN)") (class "Default")
      (node (ref "Q8") (pin "2") (pinfunction "2_2") (pintype "passive"))
      (node (ref "U$9") (pin "24") (pinfunction "XIN_24") (pintype "bidirectional"))
    )
    (net (code "55") (name "Net-(U$9-XOUT)") (class "Default")
      (node (ref "Q8") (pin "1") (pinfunction "1_1") (pintype "passive"))
      (node (ref "U$9") (pin "1") (pinfunction "XOUT_1") (pintype "bidirectional"))
    )
    (net (code "56") (name "Net-(U$14-IIN+)") (class "Default")
      (node (ref "C26") (pin "2") (pinfunction "2_2") (pintype "passive"))
      (node (ref "C27") (pin "2") (pinfunction "2_2") (pintype "passive"))
      (node (ref "R19") (pin "2") (pinfunction "2_2") (pintype "passive"))
      (node (ref "U$14") (pin "16") (pinfunction "IIN+_16") (pintype "bidirectional"))
    )
    (net (code "57") (name "Net-(U$14-IIN-)") (class "Default")
      (node (ref "C25") (pin "1") (pinfunction "1_1") (pintype "passive"))
      (node (ref "C27") (pin "1") (pinfunction "1_1") (pintype "passive"))
      (node (ref "R20") (pin "2") (pinfunction "2_2") (pintype "passive"))
      (node (ref "U$14") (pin "15") (pinfunction "IIN-_15") (pintype "bidirectional"))
    )
    (net (code "58") (name "Net-(U$14-VREFIN)") (class "Default")
      (node (ref "C19") (pin "1") (pinfunction "1_1") (pintype "passive"))
      (node (ref "U$14") (pin "11") (pinfunction "VREFOUT_11") (pintype "bidirectional"))
      (node (ref "U$14") (pin "12") (pinfunction "VREFIN_12") (pintype "bidirectional"))
    )
    (net (code "59") (name "Net-(U$14-XIN)") (class "Default")
      (node (ref "Q9") (pin "2") (pinfunction "2_2") (pintype "passive"))
      (node (ref "U$14") (pin "24") (pinfunction "XIN_24") (pintype "bidirectional"))
    )
    (net (code "60") (name "Net-(U$14-XOUT)") (class "Default")
      (node (ref "Q9") (pin "1") (pinfunction "1_1") (pintype "passive"))
      (node (ref "U$14") (pin "1") (pinfunction "XOUT_1") (pintype "bidirectional"))
    )
    (net (code "61") (name "VCC") (class "Default")
      (node (ref "5VP-CHANNEL") (pin "2") (pinfunction "S_2") (pintype "passive"))
      (node (ref "C10") (pin "1") (pinfunction "1_1") (pintype "passive"))
      (node (ref "C2") (pin "1") (pinfunction "1_1") (pintype "passive"))
      (node (ref "C20") (pin "1") (pinfunction "1_1") (pintype "passive"))
      (node (ref "C21") (pin "1") (pinfunction "1_1") (pintype "passive"))
      (node (ref "C28") (pin "+") (pinfunction "+_+") (pintype "passive"))
      (node (ref "C29") (pin "2") (pinfunction "2_2") (pintype "passive"))
      (node (ref "C3") (pin "1") (pinfunction "1_1") (pintype "passive"))
      (node (ref "C30") (pin "+") (pinfunction "+_+") (pintype "passive"))
      (node (ref "C9") (pin "1") (pinfunction "1_1") (pintype "passive"))
      (node (ref "JP1") (pin "16") (pinfunction "16_16") (pintype "passive"))
      (node (ref "JP1") (pin "17") (pinfunction "17_17") (pintype "passive"))
      (node (ref "JP1") (pin "2") (pinfunction "2_2") (pintype "passive"))
      (node (ref "JP1") (pin "7") (pinfunction "7_7") (pintype "passive"))
      (node (ref "R1") (pin "2") (pinfunction "2_2") (pintype "passive"))
      (node (ref "R3") (pin "2") (pinfunction "2_2") (pintype "passive"))
      (node (ref "U$1") (pin "1") (pinfunction "IN+_1") (pintype "bidirectional"))
      (node (ref "U$14") (pin "14") (pinfunction "VA+_14") (pintype "bidirectional"))
      (node (ref "U$14") (pin "3") (pinfunction "VD+_3") (pintype "bidirectional"))
      (node (ref "U$5") (pin "+VO") (pinfunction "+VO_+VO") (pintype "bidirectional"))
      (node (ref "U$8") (pin "14") (pinfunction "VA+_14") (pintype "bidirectional"))
      (node (ref "U$8") (pin "3") (pinfunction "VD+_3") (pintype "bidirectional"))
      (node (ref "U$9") (pin "14") (pinfunction "VA+_14") (pintype "bidirectional"))
      (node (ref "U$9") (pin "3") (pinfunction "VD+_3") (pintype "bidirectional"))
    )
    (net (code "62") (name "VSS") (class "Default")
      (node (ref "1.8VP-CHANNEL") (pin "2") (pinfunction "S_2") (pintype "passive"))
      (node (ref "U$1") (pin "2") (pinfunction "OUT+_2") (pintype "bidirectional"))
    )
    (net (code "63") (name "unconnected-(J3-Pad2)") (class "Default")
      (node (ref "J3") (pin "2") (pinfunction "2_2") (pintype "passive"))
    )
    (net (code "64") (name "unconnected-(U$8-CPUCLK-Pad2)") (class "Default")
      (node (ref "U$8") (pin "2") (pinfunction "CPUCLK_2") (pintype "bidirectional"))
    )
    (net (code "65") (name "unconnected-(U$8-E1-Pad21)") (class "Default")
      (node (ref "U$8") (pin "21") (pinfunction "E1_21") (pintype "bidirectional"))
    )
    (net (code "66") (name "unconnected-(U$8-E2-Pad22)") (class "Default")
      (node (ref "U$8") (pin "22") (pinfunction "E2_22") (pintype "bidirectional"))
    )
    (net (code "67") (name "unconnected-(U$8-E3-Pad18)") (class "Default")
      (node (ref "U$8") (pin "18") (pinfunction "E3_18") (pintype "bidirectional"))
    )
    (net (code "68") (name "unconnected-(U$8-PFMON-Pad17)") (class "Default")
      (node (ref "U$8") (pin "17") (pinfunction "PFMON_17") (pintype "bidirectional"))
    )
    (net (code "69") (name "unconnected-(U$9-CPUCLK-Pad2)") (class "Default")
      (node (ref "U$9") (pin "2") (pinfunction "CPUCLK_2") (pintype "bidirectional"))
    )
    (net (code "70") (name "unconnected-(U$9-E1-Pad21)") (class "Default")
      (node (ref "U$9") (pin "21") (pinfunction "E1_21") (pintype "bidirectional"))
    )
    (net (code "71") (name "unconnected-(U$9-E2-Pad22)") (class "Default")
      (node (ref "U$9") (pin "22") (pinfunction "E2_22") (pintype "bidirectional"))
    )
    (net (code "72") (name "unconnected-(U$9-E3-Pad18)") (class "Default")
      (node (ref "U$9") (pin "18") (pinfunction "E3_18") (pintype "bidirectional"))
    )
    (net (code "73") (name "unconnected-(U$9-PFMON-Pad17)") (class "Default")
      (node (ref "U$9") (pin "17") (pinfunction "PFMON_17") (pintype "bidirectional"))
    )
    (net (code "74") (name "unconnected-(U$14-CPUCLK-Pad2)") (class "Default")
      (node (ref "U$14") (pin "2") (pinfunction "CPUCLK_2") (pintype "bidirectional"))
    )
    (net (code "75") (name "unconnected-(U$14-E1-Pad21)") (class "Default")
      (node (ref "U$14") (pin "21") (pinfunction "E1_21") (pintype "bidirectional"))
    )
    (net (code "76") (name "unconnected-(U$14-E2-Pad22)") (class "Default")
      (node (ref "U$14") (pin "22") (pinfunction "E2_22") (pintype "bidirectional"))
    )
    (net (code "77") (name "unconnected-(U$14-E3-Pad18)") (class "Default")
      (node (ref "U$14") (pin "18") (pinfunction "E3_18") (pintype "bidirectional"))
    )
    (net (code "78") (name "unconnected-(U$14-PFMON-Pad17)") (class "Default")
      (node (ref "U$14") (pin "17") (pinfunction "PFMON_17") (pintype "bidirectional"))
    )
  )
)
